# LOW_pass_RC.net
KiCad netlist of a schematic drawn in EAGLE
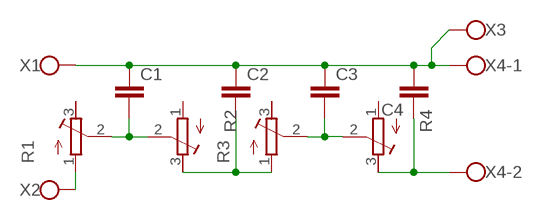
[diagram p0: schematic, sheet 1]

(export (version "E")
  (design (tool "Eeschema 10.0.6"))
  (components
    (comp (ref "C1")
      (value "C-EU050-030X075")
      (footprint "eagle-import:C050-030X075")
      (libsource (lib "eagle-import") (part "C-EU050-030X075"))
    )
    (comp (ref "C2")
      (value "C-EU050-030X075")
      (footprint "eagle-import:C050-030X075")
      (libsource (lib "eagle-import") (part "C-EU050-030X075"))
    )
    (comp (ref "C3")
      (value "C-EU050-030X075")
      (footprint "eagle-import:C050-030X075")
      (libsource (lib "eagle-import") (part "C-EU050-030X075"))
    )
    (comp (ref "C4")
      (value "C-EU050-030X075")
      (footprint "eagle-import:C050-030X075")
      (libsource (lib "eagle-import") (part "C-EU050-030X075"))
    )
    (comp (ref "R1")
      (value "R-TRIMM64W")
      (footprint "eagle-import:RTRIM64W")
      (libsource (lib "eagle-import") (part "R-TRIMM64W"))
    )
    (comp (ref "R2")
      (value "R-TRIMM64W")
      (footprint "eagle-import:RTRIM64W")
      (libsource (lib "eagle-import") (part "R-TRIMM64W"))
    )
    (comp (ref "R3")
      (value "R-TRIMM64W")
      (footprint "eagle-import:RTRIM64W")
      (libsource (lib "eagle-import") (part "R-TRIMM64W"))
    )
    (comp (ref "R4")
      (value "R-TRIMM64W")
      (footprint "eagle-import:RTRIM64W")
      (libsource (lib "eagle-import") (part "R-TRIMM64W"))
    )
    (comp (ref "X1")
      (value "W237-112")
      (footprint "eagle-import:W237-112")
      (fields (field (name "MPN") "237-112"))
      (libsource (lib "eagle-import") (part "W237-112"))
    )
    (comp (ref "X2")
      (value "W237-112")
      (footprint "eagle-import:W237-112")
      (fields (field (name "MPN") "237-112"))
      (libsource (lib "eagle-import") (part "W237-112"))
    )
    (comp (ref "X3")
      (value "W237-112")
      (footprint "eagle-import:W237-112")
      (fields (field (name "MPN") "237-112"))
      (libsource (lib "eagle-import") (part "W237-112"))
    )
    (comp (ref "X4")
      (value "W237-102")
      (footprint "eagle-import:W237-102")
      (fields (field (name "MPN") "237-102"))
      (libsource (lib "eagle-import") (part "W237-102"))
    )
  )
  (nets
    (net (code "1") (name "Net-(R1-A)") (class "Default")
      (node (ref "R1") (pin "1") (pinfunction "A_1") (pintype "passive"))
      (node (ref "X2") (pin "1") (pinfunction "KL_1") (pintype "passive"))
    )
    (net (code "2") (name "Net-(R1-S)") (class "Default")
      (node (ref "C1") (pin "2") (pinfunction "2_2") (pintype "passive"))
      (node (ref "R1") (pin "2") (pinfunction "S_2") (pintype "passive"))
      (node (ref "R2") (pin "2") (pinfunction "S_2") (pintype "passive"))
    )
    (net (code "3") (name "Net-(R2-E)") (class "Default")
      (node (ref "C2") (pin "2") (pinfunction "2_2") (pintype "passive"))
      (node (ref "R2") (pin "3") (pinfunction "E_3") (pintype "passive"))
      (node (ref "R3") (pin "1") (pinfunction "A_1") (pintype "passive"))
    )
    (net (code "4") (name "Net-(R3-S)") (class "Default")
      (node (ref "C3") (pin "2") (pinfunction "2_2") (pintype "passive"))
      (node (ref "R3") (pin "2") (pinfunction "S_2") (pintype "passive"))
      (node (ref "R4") (pin "2") (pinfunction "S_2") (pintype "passive"))
    )
    (net (code "5") (name "Net-(R4-E)") (class "Default")
      (node (ref "C4") (pin "1") (pinfunction "1_1") (pintype "passive"))
      (node (ref "R4") (pin "3") (pinfunction "E_3") (pintype "passive"))
      (node (ref "X4") (pin "2") (pinfunction "KL_2") (pintype "passive"))
    )
    (net (code "6") (name "Net-(X1-KL)") (class "Default")
      (node (ref "C1") (pin "1") (pinfunction "1_1") (pintype "passive"))
      (node (ref "C2") (pin "1") (pinfunction "1_1") (pintype "passive"))
      (node (ref "C3") (pin "1") (pinfunction "1_1") (pintype "passive"))
      (node (ref "C4") (pin "2") (pinfunction "2_2") (pintype "passive"))
      (node (ref "X1") (pin "1") (pinfunction "KL_1") (pintype "passive"))
      (node (ref "X3") (pin "1") (pinfunction "KL_1") (pintype "passive"))
      (node (ref "X4") (pin "1") (pinfunction "KL_1") (pintype "passive"))
    )
    (net (code "7") (name "unconnected-(R1-E-Pad3)") (class "Default")
      (node (ref "R1") (pin "3") (pinfunction "E_3") (pintype "passive"))
    )
    (net (code "8") (name "unconnected-(R2-A-Pad1)") (class "Default")
      (node (ref "R2") (pin "1") (pinfunction "A_1") (pintype "passive"))
    )
    (net (code "9") (name "unconnected-(R3-E-Pad3)") (class "Default")
      (node (ref "R3") (pin "3") (pinfunction "E_3") (pintype "passive"))
    )
    (net (code "10") (name "unconnected-(R4-A-Pad1)") (class "Default")
      (node (ref "R4") (pin "1") (pinfunction "A_1") (pintype "passive"))
    )
  )
)
